# Top.net
KiCad netlist of a schematic drawn in Altium Designer
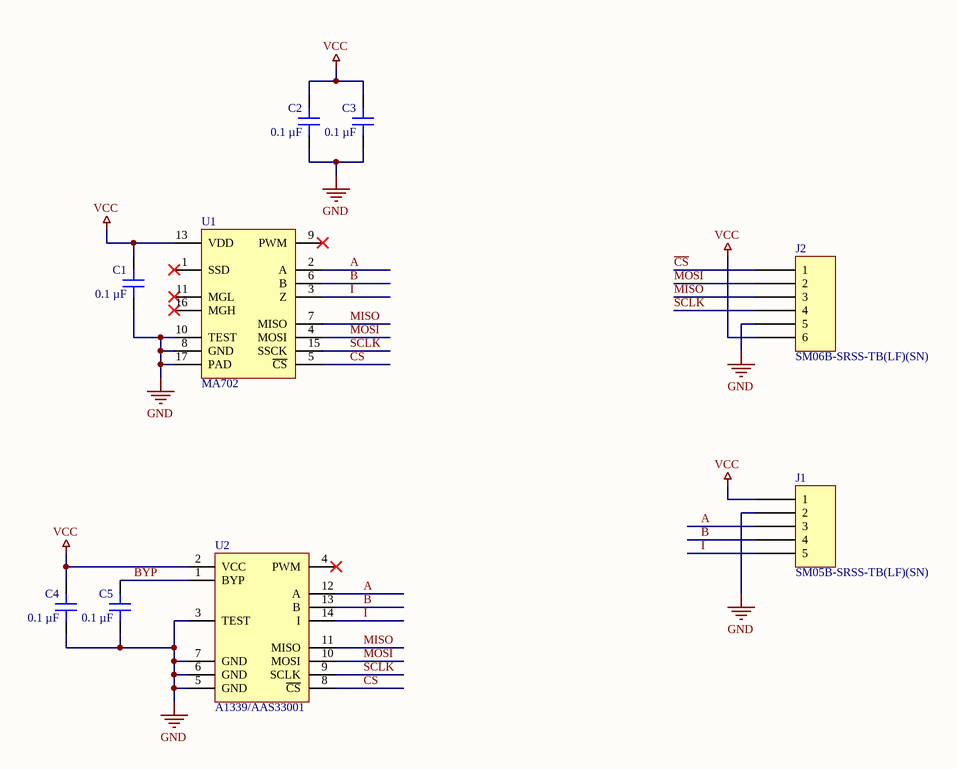
[diagram p0: Top.SchDoc]

(export (version "E")
  (design (tool "Eeschema 10.0.6"))
  (components
    (comp (ref "C1")
      (value "0.1 µF")
      (footprint "CAP 0402_1005")
      (description "CAP CER 0.1UF 25V X7R 0402")
      (fields (field (name "PART NUMBER") "C0402C104K3RAC7867") (field (name "MANUFACTURER") "KEMET"))
      (libsource (lib "Celestial Altium Library - altium_library") (part "Capacitor"))
    )
    (comp (ref "C2")
      (value "0.1 µF")
      (footprint "CAP 0402_1005")
      (description "CAP CER 0.1UF 25V X7R 0402")
      (fields (field (name "PART NUMBER") "C0402C104K3RAC7867") (field (name "MANUFACTURER") "KEMET"))
      (libsource (lib "Celestial Altium Library - altium_library") (part "Capacitor"))
    )
    (comp (ref "C3")
      (value "0.1 µF")
      (footprint "CAP 0402_1005")
      (description "CAP CER 0.1UF 25V X7R 0402")
      (fields (field (name "PART NUMBER") "C0402C104K3RAC7867") (field (name "MANUFACTURER") "KEMET"))
      (libsource (lib "Celestial Altium Library - altium_library") (part "Capacitor"))
    )
    (comp (ref "C4")
      (value "0.1 µF")
      (footprint "CAP 0402_1005")
      (description "CAP CER 0.1UF 25V X7R 0402")
      (fields (field (name "PART NUMBER") "C0402C104K3RAC7867") (field (name "MANUFACTURER") "KEMET"))
      (libsource (lib "Celestial Altium Library - altium_library") (part "Capacitor"))
    )
    (comp (ref "C5")
      (value "0.1 µF")
      (footprint "CAP 0402_1005")
      (description "CAP CER 0.1UF 25V X7R 0402")
      (fields (field (name "PART NUMBER") "C0402C104K3RAC7867") (field (name "MANUFACTURER") "KEMET"))
      (libsource (lib "Celestial Altium Library - altium_library") (part "Capacitor"))
    )
    (comp (ref "J1")
      (value "SM05B-SRSS-TB(LF)(SN)")
      (footprint "JST SM05B-SRSS-TB")
      (description "CONN HEADER SMD R/A 5POS 1MM")
      (fields (field (name "MANUFACTURER") "JST Sales America Inc."))
      (libsource (lib "Celestial Altium Library - altium_library") (part "5 Pin"))
    )
    (comp (ref "J2")
      (value "SM06B-SRSS-TB(LF)(SN)")
      (footprint "JST SM06B-SRSS-TB")
      (description "CONN HEADER SMD R/A 6POS 1MM")
      (fields (field (name "MANUFACTURER") "JST Sales America Inc."))
      (libsource (lib "Celestial Altium Library - altium_library") (part "6 Pin"))
    )
    (comp (ref "U1")
      (value "MA702")
      (footprint "IC_MA702GQ-Z")
      (description "Hall effect encoder")
      (libsource (lib "IC") (part "MA702"))
    )
    (comp (ref "U2")
      (value "A1339/AAS33001")
      (footprint "TSSOP14")
      (libsource (lib "IC") (part "A1339/AAS33001"))
    )
  )
  (nets
    (net (code "1") (name "/A") (class "Default")
      (node (ref "J1") (pin "3") (pinfunction "3_3") (pintype "passive"))
      (node (ref "U1") (pin "2") (pinfunction "A_2") (pintype "passive"))
      (node (ref "U2") (pin "12") (pinfunction "A_12") (pintype "passive"))
    )
    (net (code "2") (name "/B") (class "Default")
      (node (ref "J1") (pin "4") (pinfunction "4_4") (pintype "passive"))
      (node (ref "U1") (pin "6") (pinfunction "B_6") (pintype "passive"))
      (node (ref "U2") (pin "13") (pinfunction "B_13") (pintype "passive"))
    )
    (net (code "3") (name "/BYP") (class "Default")
      (node (ref "C5") (pin "1") (pinfunction "1_1") (pintype "passive"))
      (node (ref "U2") (pin "1") (pinfunction "BYP_1") (pintype "passive"))
    )
    (net (code "4") (name "/I") (class "Default")
      (node (ref "J1") (pin "5") (pinfunction "5_5") (pintype "passive"))
      (node (ref "U1") (pin "3") (pinfunction "Z_3") (pintype "passive"))
      (node (ref "U2") (pin "14") (pinfunction "I_14") (pintype "passive"))
    )
    (net (code "5") (name "/MISO") (class "Default")
      (node (ref "J2") (pin "3") (pinfunction "3_3") (pintype "passive"))
      (node (ref "U1") (pin "7") (pinfunction "MISO_7") (pintype "passive"))
      (node (ref "U2") (pin "11") (pinfunction "MISO_11") (pintype "passive"))
    )
    (net (code "6") (name "/MOSI") (class "Default")
      (node (ref "J2") (pin "2") (pinfunction "2_2") (pintype "passive"))
      (node (ref "U1") (pin "4") (pinfunction "MOSI_4") (pintype "passive"))
      (node (ref "U2") (pin "10") (pinfunction "MOSI_10") (pintype "passive"))
    )
    (net (code "7") (name "/SCLK") (class "Default")
      (node (ref "J2") (pin "4") (pinfunction "4_4") (pintype "passive"))
      (node (ref "U1") (pin "15") (pinfunction "SSCK_15") (pintype "passive"))
      (node (ref "U2") (pin "9") (pinfunction "SCLK_9") (pintype "passive"))
    )
    (net (code "8") (name "/~{CS}") (class "Default")
      (node (ref "J2") (pin "1") (pinfunction "1_1") (pintype "passive"))
      (node (ref "U1") (pin "5") (pinfunction "~{CS}_5") (pintype "passive"))
      (node (ref "U2") (pin "8") (pinfunction "~{CS}_8") (pintype "passive"))
    )
    (net (code "9") (name "GND") (class "Default")
      (node (ref "C1") (pin "2") (pinfunction "2_2") (pintype "passive"))
      (node (ref "C2") (pin "2") (pinfunction "2_2") (pintype "passive"))
      (node (ref "C3") (pin "2") (pinfunction "2_2") (pintype "passive"))
      (node (ref "C4") (pin "2") (pinfunction "2_2") (pintype "passive"))
      (node (ref "C5") (pin "2") (pinfunction "2_2") (pintype "passive"))
      (node (ref "J1") (pin "2") (pinfunction "2_2") (pintype "passive"))
      (node (ref "J2") (pin "5") (pinfunction "5_5") (pintype "passive"))
      (node (ref "U1") (pin "10") (pinfunction "TEST_10") (pintype "passive"))
      (node (ref "U1") (pin "17") (pinfunction "PAD_17") (pintype "passive"))
      (node (ref "U1") (pin "8") (pinfunction "GND_8") (pintype "passive"))
      (node (ref "U2") (pin "3") (pinfunction "TEST_3") (pintype "passive"))
      (node (ref "U2") (pin "5") (pinfunction "GND_5") (pintype "passive"))
      (node (ref "U2") (pin "6") (pinfunction "GND_6") (pintype "passive"))
      (node (ref "U2") (pin "7") (pinfunction "GND_7") (pintype "passive"))
    )
    (net (code "10") (name "VCC") (class "Default")
      (node (ref "C1") (pin "1") (pinfunction "1_1") (pintype "passive"))
      (node (ref "C2") (pin "1") (pinfunction "1_1") (pintype "passive"))
      (node (ref "C3") (pin "1") (pinfunction "1_1") (pintype "passive"))
      (node (ref "C4") (pin "1") (pinfunction "1_1") (pintype "passive"))
      (node (ref "J1") (pin "1") (pinfunction "1_1") (pintype "passive"))
      (node (ref "J2") (pin "6") (pinfunction "6_6") (pintype "passive"))
      (node (ref "U1") (pin "13") (pinfunction "VDD_13") (pintype "passive"))
      (node (ref "U2") (pin "2") (pinfunction "VCC_2") (pintype "passive"))
    )
    (net (code "11") (name "unconnected-(U1-MGH-Pad16)") (class "Default")
      (node (ref "U1") (pin "16") (pinfunction "MGH_16") (pintype "passive+no_connect"))
    )
    (net (code "12") (name "unconnected-(U1-MGL-Pad11)") (class "Default")
      (node (ref "U1") (pin "11") (pinfunction "MGL_11") (pintype "passive+no_connect"))
    )
    (net (code "13") (name "unconnected-(U1-PWM-Pad9)") (class "Default")
      (node (ref "U1") (pin "9") (pinfunction "PWM_9") (pintype "passive+no_connect"))
    )
    (net (code "14") (name "unconnected-(U1-SSD-Pad1)") (class "Default")
      (node (ref "U1") (pin "1") (pinfunction "SSD_1") (pintype "passive+no_connect"))
    )
    (net (code "15") (name "unconnected-(U2-PWM-Pad4)") (class "Default")
      (node (ref "U2") (pin "4") (pinfunction "PWM_4") (pintype "passive+no_connect"))
    )
  )
)
